# D5035-50.net
KiCad netlist of a schematic drawn in Altium Designer
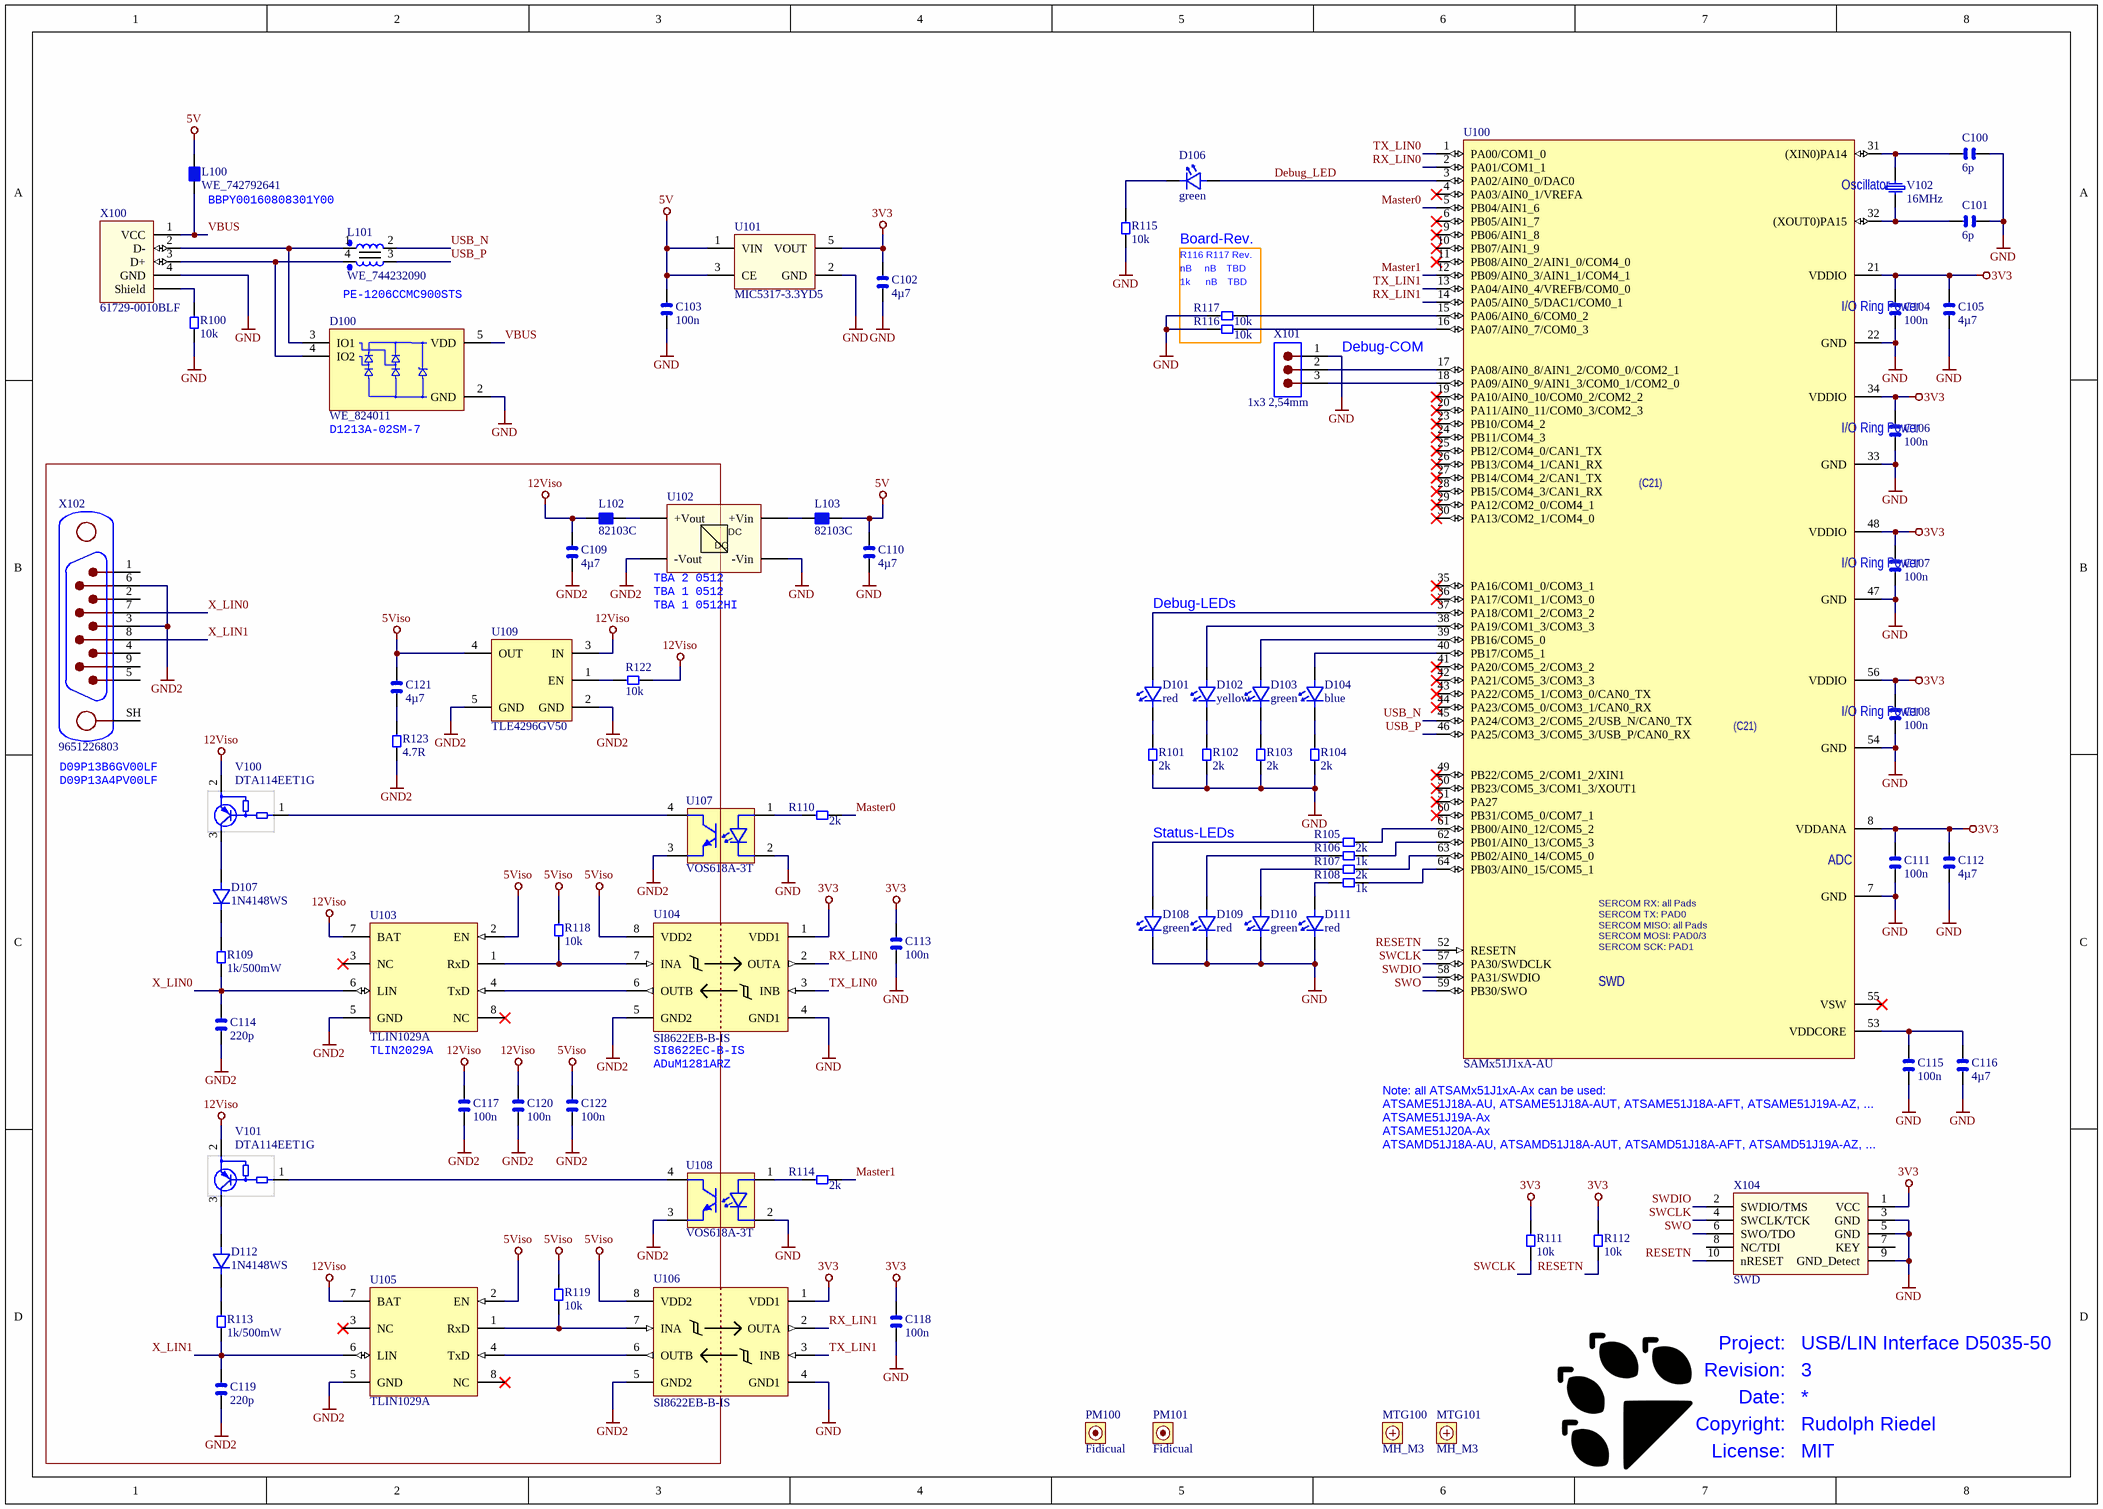
[diagram p0: D5035-50.SchDoc]

(export (version "E")
  (design (tool "Eeschema 10.0.6"))
  (components
    (comp (ref "C100")
      (value "6p")
      (footprint "CAPC1608X09L")
      (description "0603 Chip Capacitor")
      (fields (field (name "PART NUMBER") "CAPC_0603") (field (name "EDITOR") "rriedel"))
      (libsource (lib "HW-Labor_GF") (part "CAP_2_V2"))
    )
    (comp (ref "C101")
      (value "6p")
      (footprint "CAPC1608X09L")
      (description "0603 Chip Capacitor")
      (fields (field (name "PART NUMBER") "CAPC_0603") (field (name "EDITOR") "rriedel"))
      (libsource (lib "HW-Labor_GF") (part "CAP_2_V2"))
    )
    (comp (ref "C102")
      (value "4µ7")
      (footprint "CAPC2012X14L")
      (description "0805 Chip Capacitor")
      (fields (field (name "PART NUMBER") "CAPC_0805") (field (name "EDITOR") "rriedel"))
      (libsource (lib "HW-Labor_GF") (part "CAP_2_V2"))
    )
    (comp (ref "C103")
      (value "100n")
      (footprint "CAPC1608X09L")
      (description "0603 Chip Capacitor")
      (fields (field (name "PART NUMBER") "CAPC_0603") (field (name "EDITOR") "rriedel"))
      (libsource (lib "HW-Labor_GF") (part "CAP_2_V2"))
    )
    (comp (ref "C104")
      (value "100n")
      (footprint "CAPC1608X09L")
      (description "0603 Chip Capacitor")
      (fields (field (name "PART NUMBER") "CAPC_0603") (field (name "EDITOR") "rriedel"))
      (libsource (lib "HW-Labor_GF") (part "CAP_2_V2"))
    )
    (comp (ref "C105")
      (value "4µ7")
      (footprint "CAPC2012X14L")
      (description "0805 Chip Capacitor")
      (fields (field (name "PART NUMBER") "CAPC_0805") (field (name "EDITOR") "rriedel"))
      (libsource (lib "HW-Labor_GF") (part "CAP_2_V2"))
    )
    (comp (ref "C106")
      (value "100n")
      (footprint "CAPC1608X09L")
      (description "0603 Chip Capacitor")
      (fields (field (name "PART NUMBER") "CAPC_0603") (field (name "EDITOR") "rriedel"))
      (libsource (lib "HW-Labor_GF") (part "CAP_2_V2"))
    )
    (comp (ref "C107")
      (value "100n")
      (footprint "CAPC1608X09L")
      (description "0603 Chip Capacitor")
      (fields (field (name "PART NUMBER") "CAPC_0603") (field (name "EDITOR") "rriedel"))
      (libsource (lib "HW-Labor_GF") (part "CAP_2_V2"))
    )
    (comp (ref "C108")
      (value "100n")
      (footprint "CAPC1608X09L")
      (description "0603 Chip Capacitor")
      (fields (field (name "PART NUMBER") "CAPC_0603") (field (name "EDITOR") "rriedel"))
      (libsource (lib "HW-Labor_GF") (part "CAP_2_V2"))
    )
    (comp (ref "C109")
      (value "4µ7")
      (footprint "CAPC2012X14L")
      (description "0805 Chip Capacitor")
      (fields (field (name "PART NUMBER") "CAPC_0805") (field (name "EDITOR") "rriedel"))
      (libsource (lib "HW-Labor_GF") (part "CAP_2_V2"))
    )
    (comp (ref "C110")
      (value "4µ7")
      (footprint "CAPC2012X14L")
      (description "0805 Chip Capacitor")
      (fields (field (name "PART NUMBER") "CAPC_0805") (field (name "EDITOR") "rriedel"))
      (libsource (lib "HW-Labor_GF") (part "CAP_2_V2"))
    )
    (comp (ref "C111")
      (value "100n")
      (footprint "CAPC1608X09L")
      (description "0603 Chip Capacitor")
      (fields (field (name "PART NUMBER") "CAPC_0603") (field (name "EDITOR") "rriedel"))
      (libsource (lib "HW-Labor_GF") (part "CAP_2_V2"))
    )
    (comp (ref "C112")
      (value "4µ7")
      (footprint "CAPC2012X14L")
      (description "0805 Chip Capacitor")
      (fields (field (name "PART NUMBER") "CAPC_0805") (field (name "EDITOR") "rriedel"))
      (libsource (lib "HW-Labor_GF") (part "CAP_2_V2"))
    )
    (comp (ref "C113")
      (value "100n")
      (footprint "CAPC1608X09L")
      (description "0603 Chip Capacitor")
      (fields (field (name "PART NUMBER") "CAPC_0603") (field (name "EDITOR") "rriedel"))
      (libsource (lib "HW-Labor_GF") (part "CAP_2_V2"))
    )
    (comp (ref "C114")
      (value "220p")
      (footprint "CAPC2012X14L")
      (description "0805 Chip Capacitor")
      (fields (field (name "PART NUMBER") "CAPC_0805") (field (name "EDITOR") "rriedel"))
      (libsource (lib "HW-Labor_GF") (part "CAP_2_V2"))
    )
    (comp (ref "C115")
      (value "100n")
      (footprint "CAPC1608X09L")
      (description "0603 Chip Capacitor")
      (fields (field (name "PART NUMBER") "CAPC_0603") (field (name "EDITOR") "rriedel"))
      (libsource (lib "HW-Labor_GF") (part "CAP_2_V2"))
    )
    (comp (ref "C116")
      (value "4µ7")
      (footprint "CAPC2012X14L")
      (description "0805 Chip Capacitor")
      (fields (field (name "PART NUMBER") "CAPC_0805") (field (name "EDITOR") "rriedel"))
      (libsource (lib "HW-Labor_GF") (part "CAP_2_V2"))
    )
    (comp (ref "C117")
      (value "100n")
      (footprint "CAPC1608X09L")
      (description "0603 Chip Capacitor")
      (fields (field (name "PART NUMBER") "CAPC_0603") (field (name "EDITOR") "rriedel"))
      (libsource (lib "HW-Labor_GF") (part "CAP_2_V2"))
    )
    (comp (ref "C118")
      (value "100n")
      (footprint "CAPC1608X09L")
      (description "0603 Chip Capacitor")
      (fields (field (name "PART NUMBER") "CAPC_0603") (field (name "EDITOR") "rriedel"))
      (libsource (lib "HW-Labor_GF") (part "CAP_2_V2"))
    )
    (comp (ref "C119")
      (value "220p")
      (footprint "CAPC2012X14L")
      (description "0805 Chip Capacitor")
      (fields (field (name "PART NUMBER") "CAPC_0805") (field (name "EDITOR") "rriedel"))
      (libsource (lib "HW-Labor_GF") (part "CAP_2_V2"))
    )
    (comp (ref "C120")
      (value "100n")
      (footprint "CAPC1608X09L")
      (description "0603 Chip Capacitor")
      (fields (field (name "PART NUMBER") "CAPC_0603") (field (name "EDITOR") "rriedel"))
      (libsource (lib "HW-Labor_GF") (part "CAP_2_V2"))
    )
    (comp (ref "C121")
      (value "4µ7")
      (footprint "CAPC2012X14L")
      (description "0805 Chip Capacitor")
      (fields (field (name "PART NUMBER") "CAPC_0805") (field (name "EDITOR") "rriedel"))
      (libsource (lib "HW-Labor_GF") (part "CAP_2_V2"))
    )
    (comp (ref "C122")
      (value "100n")
      (footprint "CAPC1608X09L")
      (description "0603 Chip Capacitor")
      (fields (field (name "PART NUMBER") "CAPC_0603") (field (name "EDITOR") "rriedel"))
      (libsource (lib "HW-Labor_GF") (part "CAP_2_V2"))
    )
    (comp (ref "D100")
      (value "WE_824011")
      (footprint "SOT95P280X110-5N")
      (description "TVS Diode Array WE-TVS")
      (fields
        (field (name "MANUFACTURER") "Wuerth")
        (field (name "DISTRIBUTOR_1_PART_NUMBER") "732-4465-1-ND")
        (field (name "EDITOR") "rriedel")
      )
      (libsource (lib "HW-Labor_GF") (part "WE-824011"))
    )
    (comp (ref "D101")
      (value "red")
      (footprint "DIOC1608X06N_LED")
      (description "LED, 0603")
      (fields (field (name "PART NUMBER") "LED_0603") (field (name "EDITOR") "rriedel"))
      (libsource (lib "HW-Labor_GF") (part "LED_generic"))
    )
    (comp (ref "D102")
      (value "yellow")
      (footprint "DIOC1608X06N_LED")
      (description "LED, 0603")
      (fields (field (name "PART NUMBER") "LED_0603") (field (name "EDITOR") "rriedel"))
      (libsource (lib "HW-Labor_GF") (part "LED_generic"))
    )
    (comp (ref "D103")
      (value "green")
      (footprint "DIOC1608X06N_LED")
      (description "LED, 0603")
      (fields (field (name "PART NUMBER") "LED_0603") (field (name "EDITOR") "rriedel"))
      (libsource (lib "HW-Labor_GF") (part "LED_generic"))
    )
    (comp (ref "D104")
      (value "blue")
      (footprint "DIOC1608X06N_LED")
      (description "LED, 0603")
      (fields (field (name "PART NUMBER") "LED_0603") (field (name "EDITOR") "rriedel"))
      (libsource (lib "HW-Labor_GF") (part "LED_generic"))
    )
    (comp (ref "D106")
      (value "green")
      (footprint "DIOC1608X06N_LED")
      (description "LED, 0603")
      (fields (field (name "PART NUMBER") "LED_0603") (field (name "EDITOR") "rriedel"))
      (libsource (lib "HW-Labor_GF") (part "LED_generic"))
    )
    (comp (ref "D107")
      (value "1N4148WS")
      (footprint "SOD323")
      (description "Small Signal Diode IF 0.15A, VR 75V, SOD323F")
      (fields (field (name "DISTRIBUTOR_1_PART_NUMBER") "C2128") (field (name "EDITOR") "rriedel"))
      (libsource (lib "HW-Labor_GF") (part "Diode_A2_K1"))
    )
    (comp (ref "D108")
      (value "green")
      (footprint "DIOC1608X06N_LED")
      (description "LED, 0603")
      (fields (field (name "PART NUMBER") "LED_0603") (field (name "EDITOR") "rriedel"))
      (libsource (lib "HW-Labor_GF") (part "LED_generic"))
    )
    (comp (ref "D109")
      (value "red")
      (footprint "DIOC1608X06N_LED")
      (description "LED, 0603")
      (fields (field (name "PART NUMBER") "LED_0603") (field (name "EDITOR") "rriedel"))
      (libsource (lib "HW-Labor_GF") (part "LED_generic"))
    )
    (comp (ref "D110")
      (value "green")
      (footprint "DIOC1608X06N_LED")
      (description "LED, 0603")
      (fields (field (name "PART NUMBER") "LED_0603") (field (name "EDITOR") "rriedel"))
      (libsource (lib "HW-Labor_GF") (part "LED_generic"))
    )
    (comp (ref "D111")
      (value "red")
      (footprint "DIOC1608X06N_LED")
      (description "LED, 0603")
      (fields (field (name "PART NUMBER") "LED_0603") (field (name "EDITOR") "rriedel"))
      (libsource (lib "HW-Labor_GF") (part "LED_generic"))
    )
    (comp (ref "D112")
      (value "1N4148WS")
      (footprint "SOD323")
      (description "Small Signal Diode IF 0.15A, VR 75V, SOD323F")
      (fields (field (name "DISTRIBUTOR_1_PART_NUMBER") "C2128") (field (name "EDITOR") "rriedel"))
      (libsource (lib "HW-Labor_GF") (part "Diode_A2_K1"))
    )
    (comp (ref "L100")
      (value "WE_742792641")
      (footprint "INDC1608X06L")
      (description "SMT EMI suppression ferrite bead WE-CBF")
      (fields
        (field (name "MANUFACTURER") "Wuerth")
        (field (name "DISTRIBUTOR_1_PART_NUMBER") "732-1592-1-ND")
        (field (name "EDITOR") "rriedel")
      )
      (libsource (lib "HW-Labor_GF") (part "IND_2_V1"))
    )
    (comp (ref "L101")
      (value "WE_744232090")
      (footprint "WE_744232090")
      (description "SMD common mode noise suppressor WE-CNSW")
      (fields
        (field (name "MANUFACTURER") "Wuerth")
        (field (name "DISTRIBUTOR_1_PART_NUMBER") "732-1469-1-ND")
        (field (name "EDITOR") "rriedel")
      )
      (libsource (lib "HW-Labor_GF") (part "WE_744232090"))
    )
    (comp (ref "L102")
      (value "82103C")
      (footprint "Murata_8200C")
      (description "10µH, 0,5A, 400mR")
      (fields
        (field (name "MANUFACTURER") "Murata")
        (field (name "DISTRIBUTOR_1_PART_NUMBER") "811-2473-1-ND")
        (field (name "EDITOR") "rriedel")
      )
      (libsource (lib "HW-Labor_GF") (part "IND_2_V1"))
    )
    (comp (ref "L103")
      (value "82103C")
      (footprint "Murata_8200C")
      (description "10µH, 0,5A, 400mR")
      (fields
        (field (name "MANUFACTURER") "Murata")
        (field (name "DISTRIBUTOR_1_PART_NUMBER") "811-2473-1-ND")
        (field (name "EDITOR") "rriedel")
      )
      (libsource (lib "HW-Labor_GF") (part "IND_2_V1"))
    )
    (comp (ref "MTG100")
      (value "MH_M3")
      (footprint "HOLE_3_2MM")
      (description "Mounting-Hole for M3 screws")
      (fields (field (name "EDITOR") "rriedel"))
      (libsource (lib "HW-Labor_GF") (part "MTG_V1"))
    )
    (comp (ref "MTG101")
      (value "MH_M3")
      (footprint "HOLE_3_2MM")
      (description "Mounting-Hole for M3 screws")
      (fields (field (name "EDITOR") "rriedel"))
      (libsource (lib "HW-Labor_GF") (part "MTG_V1"))
    )
    (comp (ref "PM100")
      (value "Fidicual")
      (footprint "PM100")
      (fields (field (name "PART NUMBER") "PM100") (field (name "EDITOR") "rriedel"))
      (libsource (lib "HW-Labor_GF") (part "PM100"))
    )
    (comp (ref "PM101")
      (value "Fidicual")
      (footprint "PM100")
      (fields (field (name "PART NUMBER") "PM100") (field (name "EDITOR") "rriedel"))
      (libsource (lib "HW-Labor_GF") (part "PM100"))
    )
    (comp (ref "R100")
      (value "10k")
      (footprint "RESC1608X06L")
      (description "0603 Chip Resistor")
      (fields (field (name "PART NUMBER") "RESC_0603") (field (name "EDITOR") "rriedel"))
      (libsource (lib "HW-Labor_GF") (part "RES_2_V2"))
    )
    (comp (ref "R101")
      (value "2k")
      (footprint "RESC1608X06L")
      (description "0603 Chip Resistor")
      (fields (field (name "PART NUMBER") "RESC_0603") (field (name "EDITOR") "rriedel"))
      (libsource (lib "HW-Labor_GF") (part "RES_2_V2"))
    )
    (comp (ref "R102")
      (value "2k")
      (footprint "RESC1608X06L")
      (description "0603 Chip Resistor")
      (fields (field (name "PART NUMBER") "RESC_0603") (field (name "EDITOR") "rriedel"))
      (libsource (lib "HW-Labor_GF") (part "RES_2_V2"))
    )
    (comp (ref "R103")
      (value "2k")
      (footprint "RESC1608X06L")
      (description "0603 Chip Resistor")
      (fields (field (name "PART NUMBER") "RESC_0603") (field (name "EDITOR") "rriedel"))
      (libsource (lib "HW-Labor_GF") (part "RES_2_V2"))
    )
    (comp (ref "R104")
      (value "2k")
      (footprint "RESC1608X06L")
      (description "0603 Chip Resistor")
      (fields (field (name "PART NUMBER") "RESC_0603") (field (name "EDITOR") "rriedel"))
      (libsource (lib "HW-Labor_GF") (part "RES_2_V2"))
    )
    (comp (ref "R105")
      (value "2k")
      (footprint "RESC1608X06L")
      (description "0603 Chip Resistor")
      (fields (field (name "PART NUMBER") "RESC_0603") (field (name "EDITOR") "rriedel"))
      (libsource (lib "HW-Labor_GF") (part "RES_2_V2"))
    )
    (comp (ref "R106")
      (value "1k")
      (footprint "RESC1608X06L")
      (description "0603 Chip Resistor")
      (fields (field (name "PART NUMBER") "RESC_0603") (field (name "EDITOR") "rriedel"))
      (libsource (lib "HW-Labor_GF") (part "RES_2_V2"))
    )
    (comp (ref "R107")
      (value "2k")
      (footprint "RESC1608X06L")
      (description "0603 Chip Resistor")
      (fields (field (name "PART NUMBER") "RESC_0603") (field (name "EDITOR") "rriedel"))
      (libsource (lib "HW-Labor_GF") (part "RES_2_V2"))
    )
    (comp (ref "R108")
      (value "1k")
      (footprint "RESC1608X06L")
      (description "0603 Chip Resistor")
      (fields (field (name "PART NUMBER") "RESC_0603") (field (name "EDITOR") "rriedel"))
      (libsource (lib "HW-Labor_GF") (part "RES_2_V2"))
    )
    (comp (ref "R109")
      (value "1k/500mW")
      (footprint "RESC2012X06L")
      (description "0805 Chip Resistor")
      (fields (field (name "PART NUMBER") "RESC_0805") (field (name "EDITOR") "rriedel"))
      (libsource (lib "HW-Labor_GF") (part "RES_2_V2"))
    )
    (comp (ref "R110")
      (value "2k")
      (footprint "RESC1608X06L")
      (description "0603 Chip Resistor")
      (fields (field (name "PART NUMBER") "RESC_0603") (field (name "EDITOR") "rriedel"))
      (libsource (lib "HW-Labor_GF") (part "RES_2_V2"))
    )
    (comp (ref "R111")
      (value "10k")
      (footprint "RESC1608X06L")
      (description "0603 Chip Resistor")
      (fields (field (name "PART NUMBER") "RESC_0603") (field (name "EDITOR") "rriedel"))
      (libsource (lib "HW-Labor_GF") (part "RES_2_V2"))
    )
    (comp (ref "R112")
      (value "10k")
      (footprint "RESC1608X06L")
      (description "0603 Chip Resistor")
      (fields (field (name "PART NUMBER") "RESC_0603") (field (name "EDITOR") "rriedel"))
      (libsource (lib "HW-Labor_GF") (part "RES_2_V2"))
    )
    (comp (ref "R113")
      (value "1k/500mW")
      (footprint "RESC2012X06L")
      (description "0805 Chip Resistor")
      (fields (field (name "PART NUMBER") "RESC_0805") (field (name "EDITOR") "rriedel"))
      (libsource (lib "HW-Labor_GF") (part "RES_2_V2"))
    )
    (comp (ref "R114")
      (value "2k")
      (footprint "RESC1608X06L")
      (description "0603 Chip Resistor")
      (fields (field (name "PART NUMBER") "RESC_0603") (field (name "EDITOR") "rriedel"))
      (libsource (lib "HW-Labor_GF") (part "RES_2_V2"))
    )
    (comp (ref "R115")
      (value "10k")
      (footprint "RESC1608X06L")
      (description "0603 Chip Resistor")
      (fields (field (name "PART NUMBER") "RESC_0603") (field (name "EDITOR") "rriedel"))
      (libsource (lib "HW-Labor_GF") (part "RES_2_V2"))
    )
    (comp (ref "R116")
      (value "10k")
      (footprint "RESC1608X06L")
      (description "0603 Chip Resistor")
      (fields (field (name "PART NUMBER") "RESC_0603") (field (name "EDITOR") "rriedel"))
      (libsource (lib "HW-Labor_GF") (part "RES_2_V2"))
    )
    (comp (ref "R117")
      (value "10k")
      (footprint "RESC1608X06L")
      (description "0603 Chip Resistor")
      (fields (field (name "PART NUMBER") "RESC_0603") (field (name "EDITOR") "rriedel"))
      (libsource (lib "HW-Labor_GF") (part "RES_2_V2"))
    )
    (comp (ref "R118")
      (value "10k")
      (footprint "RESC1608X06L")
      (description "0603 Chip Resistor")
      (fields (field (name "PART NUMBER") "RESC_0603") (field (name "EDITOR") "rriedel"))
      (libsource (lib "HW-Labor_GF") (part "RES_2_V2"))
    )
    (comp (ref "R119")
      (value "10k")
      (footprint "RESC1608X06L")
      (description "0603 Chip Resistor")
      (fields (field (name "PART NUMBER") "RESC_0603") (field (name "EDITOR") "rriedel"))
      (libsource (lib "HW-Labor_GF") (part "RES_2_V2"))
    )
    (comp (ref "R122")
      (value "10k")
      (footprint "RESC1608X06L")
      (description "0603 Chip Resistor")
      (fields (field (name "PART NUMBER") "RESC_0603") (field (name "EDITOR") "rriedel"))
      (libsource (lib "HW-Labor_GF") (part "RES_2_V2"))
    )
    (comp (ref "R123")
      (value "4.7R")
      (footprint "RESC1608X06L")
      (description "0603 Chip Resistor")
      (fields (field (name "PART NUMBER") "RESC_0603") (field (name "EDITOR") "rriedel"))
      (libsource (lib "HW-Labor_GF") (part "RES_2_V2"))
    )
    (comp (ref "U100")
      (value "SAMx51J1xA-AU")
      (footprint "TSQFP50P1200X1200X120-64N")
      (description "32-bit Microcontroller, 120MHz Cortex M4-F, 512k FLASH,  2x CAN-FD, -40…85°C")
      (fields
        (field (name "PART NUMBER") "SAME51J19A-AU")
        (field (name "MANUFACTURER") "Microchip")
        (field (name "EDITOR") "rriedel")
      )
      (libsource (lib "HW-Labor_GF") (part "SAME5xJxxA-AUx"))
    )
    (comp (ref "U101")
      (value "MIC5317-3.3YD5")
      (footprint "SOT95P280X110-5N")
      (description "100 mA LDO,  Vout= 3,3V, -40°C..125°C")
      (fields (field (name "MANUFACTURER") "Microchip") (field (name "EDITOR") "rriedel"))
      (libsource (lib "HW-Labor_GF") (part "LDO_SOT23-5"))
    )
    (comp (ref "U102")
      (value "~")
      (footprint "TBA1/TBA2")
      (description "Isolated Single Output DC-DC Converters 5V/12V")
      (fields (field (name "PART NUMBER") "TBA 2-0512") (field (name "EDITOR") "rriedel"))
      (libsource (lib "HW-Labor_GF") (part "MER1SxxxxC"))
    )
    (comp (ref "U103")
      (value "TLIN1029A")
      (footprint "SOIC127P600X175-8N")
      (description "LIN transceiver")
      (fields
        (field (name "MANUFACTURER") "TI")
        (field (name "DISTRIBUTOR_1_PART_NUMBER") "595-TLIN1029ADRQ1")
        (field (name "EDITOR") "rriedel")
      )
      (libsource (lib "HW-Labor_GF") (part "TLIN1029A"))
    )
    (comp (ref "U104")
      (value "SI8622EB-B-IS")
      (footprint "SOIC127P600X175-8N")
      (description "Dual channel digital isolator, 150Mbit, 2,5kV")
      (fields
        (field (name "MANUFACTURER") "Silicon Labs")
        (field (name "DISTRIBUTOR_1_PART_NUMBER") "336-5209-1-ND")
        (field (name "EDITOR") "rriedel")
      )
      (libsource (lib "HW-Labor_GF") (part "SI8622"))
    )
    (comp (ref "U105")
      (value "TLIN1029A")
      (footprint "SOIC127P600X175-8N")
      (description "LIN transceiver")
      (fields
        (field (name "MANUFACTURER") "TI")
        (field (name "DISTRIBUTOR_1_PART_NUMBER") "595-TLIN1029ADRQ1")
        (field (name "EDITOR") "rriedel")
      )
      (libsource (lib "HW-Labor_GF") (part "TLIN1029A"))
    )
    (comp (ref "U106")
      (value "SI8622EB-B-IS")
      (footprint "SOIC127P600X175-8N")
      (description "Dual channel digital isolator, 150Mbit, 2,5kV")
      (fields
        (field (name "MANUFACTURER") "Silicon Labs")
        (field (name "DISTRIBUTOR_1_PART_NUMBER") "336-5209-1-ND")
        (field (name "EDITOR") "rriedel")
      )
      (libsource (lib "HW-Labor_GF") (part "SI8622"))
    )
    (comp (ref "U107")
      (value "VOS618A-3T")
      (footprint "SSOP-4")
      (description "Optocoupler, Phototransistor Output, Low Input Current, SSOP-4")
      (fields
        (field (name "MANUFACTURER") "Vishay")
        (field (name "DISTRIBUTOR_1_PART_NUMBER") "VOS618A-3TCT-ND‎")
        (field (name "EDITOR") "rriedel")
      )
      (libsource (lib "HW-Labor_GF") (part "VOS618A"))
    )
    (comp (ref "U108")
      (value "VOS618A-3T")
      (footprint "SSOP-4")
      (description "Optocoupler, Phototransistor Output, Low Input Current, SSOP-4")
      (fields
        (field (name "MANUFACTURER") "Vishay")
        (field (name "DISTRIBUTOR_1_PART_NUMBER") "VOS618A-3TCT-ND‎")
        (field (name "EDITOR") "rriedel")
      )
      (libsource (lib "HW-Labor_GF") (part "VOS618A"))
    )
    (comp (ref "U109")
      (value "TLE4296GV50")
      (footprint "INF-PG-SCT595V")
      (description "30 mA LDO, Vout = 5,0V, 4%")
      (fields (field (name "MANUFACTURER") "Infineon") (field (name "EDITOR") "rriedel"))
      (libsource (lib "HW-Labor_GF") (part "TLE4295GVxx"))
    )
    (comp (ref "V100")
      (value "DTA114EET1G")
      (footprint "SOT50P162X60-3N")
      (description "PNP Transistor with Resistors (10kΩ, 10kΩ)  VCE= 50V, IC=100mA, SOT23, AEC Q101")
      (fields (field (name "EDITOR") "rriedel"))
      (libsource (lib "HW-Labor_GF") (part "PNP_Digital"))
    )
    (comp (ref "V101")
      (value "DTA114EET1G")
      (footprint "SOT50P162X60-3N")
      (description "PNP Transistor with Resistors (10kΩ, 10kΩ)  VCE= 50V, IC=100mA, SOT23, AEC Q101")
      (fields (field (name "EDITOR") "rriedel"))
      (libsource (lib "HW-Labor_GF") (part "PNP_Digital"))
    )
    (comp (ref "V102")
      (value "16MHz")
      (footprint "NX3225Gx")
      (description "16.000MHz Crystal SMD, 3.2x2.5mm, 8pF, 50ppm,  -40..+150°C")
      (fields
        (field (name "PART NUMBER") "NX3225GB-16.000000MHZ")
        (field (name "MANUFACTURER") "NDK")
        (field (name "EDITOR") "rriedel")
      )
      (libsource (lib "HW-Labor_GF") (part "XTAL_2_V1"))
    )
    (comp (ref "X100")
      (value "61729-0010BLF")
      (footprint "61729-xxxxxLF")
      (description "USB-B socket, THT")
      (fields
        (field (name "MANUFACTURER") "Amphenol")
        (field (name "DISTRIBUTOR_1_PART_NUMBER") "609-1039-ND")
        (field (name "EDITOR") "rriedel")
      )
      (libsource (lib "HW-Labor_GF") (part "USB"))
    )
    (comp (ref "X101")
      (value "1x3 2,54mm")
      (footprint "PINH_1x03_2_54mm")
      (description "Pin-Header 2,54 mm 3pins")
      (fields (field (name "PART NUMBER") "PINH_1x3_2_54") (field (name "EDITOR") "rriedel"))
      (libsource (lib "HW-Labor_GF") (part "CONM_1x3_V2"))
    )
    (comp (ref "X102")
      (value "9651226803")
      (footprint "09651226803")
      (description "D-Sub, 9 pin, male, right angle")
      (fields
        (field (name "MANUFACTURER") "Harting")
        (field (name "DISTRIBUTOR_1_PART_NUMBER") "2752007")
        (field (name "EDITOR") "rriedel")
      )
      (libsource (lib "HW-Labor_GF") (part "D_Sub_9_Male"))
    )
    (comp (ref "X104")
      (value "SWD")
      (footprint "FTSH-105-01-L-DV-K")
      (description "ARM Debug-Header 2x5 1,27 mm")
      (fields (field (name "EDITOR") "rriedel"))
      (libsource (lib "HW-Labor_GF") (part "SWD"))
    )
  )
  (nets
    (net (code "1") (name "/Debug_LED") (class "Default")
      (node (ref "D106") (pin "2") (pinfunction "2_2") (pintype "passive"))
      (node (ref "U100") (pin "3") (pinfunction "PA02/AIN0_0/DAC0_3") (pintype "bidirectional"))
    )
    (net (code "2") (name "/Master0") (class "Default")
      (node (ref "R110") (pin "1") (pinfunction "1_1") (pintype "passive"))
      (node (ref "U100") (pin "5") (pinfunction "PB04/AIN1_6_5") (pintype "bidirectional"))
    )
    (net (code "3") (name "/Master1") (class "Default")
      (node (ref "R114") (pin "1") (pinfunction "1_1") (pintype "passive"))
      (node (ref "U100") (pin "12") (pinfunction "PB09/AIN0_3/AIN1_1/COM4_1_12") (pintype "bidirectional"))
    )
    (net (code "4") (name "/RESETN") (class "Default")
      (node (ref "R112") (pin "2") (pinfunction "2_2") (pintype "passive"))
      (node (ref "U100") (pin "52") (pinfunction "RESETN_52") (pintype "input"))
      (node (ref "X104") (pin "10") (pinfunction "nRESET_10") (pintype "passive"))
    )
    (net (code "5") (name "/RX_LIN0") (class "Default")
      (node (ref "U100") (pin "2") (pinfunction "PA01/COM1_1_2") (pintype "bidirectional"))
      (node (ref "U104") (pin "2") (pinfunction "OUTA_2") (pintype "output"))
    )
    (net (code "6") (name "/RX_LIN1") (class "Default")
      (node (ref "U100") (pin "14") (pinfunction "PA05/AIN0_5/DAC1/COM0_1_14") (pintype "bidirectional"))
      (node (ref "U106") (pin "2") (pinfunction "OUTA_2") (pintype "output"))
    )
    (net (code "7") (name "/SWCLK") (class "Default")
      (node (ref "R111") (pin "2") (pinfunction "2_2") (pintype "passive"))
      (node (ref "U100") (pin "57") (pinfunction "PA30/SWDCLK_57") (pintype "bidirectional"))
      (node (ref "X104") (pin "4") (pinfunction "SWCLK/TCK_4") (pintype "passive"))
    )
    (net (code "8") (name "/SWDIO") (class "Default")
      (node (ref "U100") (pin "58") (pinfunction "PA31/SWDIO_58") (pintype "bidirectional"))
      (node (ref "X104") (pin "2") (pinfunction "SWDIO/TMS_2") (pintype "passive"))
    )
    (net (code "9") (name "/SWO") (class "Default")
      (node (ref "U100") (pin "59") (pinfunction "PB30/SWO_59") (pintype "bidirectional"))
      (node (ref "X104") (pin "6") (pinfunction "SWO/TDO_6") (pintype "passive"))
    )
    (net (code "10") (name "/TX_LIN0") (class "Default")
      (node (ref "U100") (pin "1") (pinfunction "PA00/COM1_0_1") (pintype "bidirectional"))
      (node (ref "U104") (pin "3") (pinfunction "INB_3") (pintype "input"))
    )
    (net (code "11") (name "/TX_LIN1") (class "Default")
      (node (ref "U100") (pin "13") (pinfunction "PA04/AIN0_4/VREFB/COM0_0_13") (pintype "bidirectional"))
      (node (ref "U106") (pin "3") (pinfunction "INB_3") (pintype "input"))
    )
    (net (code "12") (name "/USB_N") (class "Default")
      (node (ref "L101") (pin "2") (pinfunction "2_2") (pintype "passive"))
      (node (ref "U100") (pin "45") (pinfunction "PA24/COM3_2/COM5_2/USB_N/CAN0_TX_45") (pintype "bidirectional"))
    )
    (net (code "13") (name "/USB_P") (class "Default")
      (node (ref "L101") (pin "3") (pinfunction "3_3") (pintype "passive"))
      (node (ref "U100") (pin "46") (pinfunction "PA25/COM3_3/COM5_3/USB_P/CAN0_RX_46") (pintype "bidirectional"))
    )
    (net (code "14") (name "/VBUS") (class "Default")
      (node (ref "D100") (pin "5") (pinfunction "VDD_5") (pintype "passive"))
      (node (ref "L100") (pin "1") (pinfunction "1_1") (pintype "passive"))
      (node (ref "X100") (pin "1") (pinfunction "VCC_1") (pintype "power_in"))
    )
    (net (code "15") (name "/X_LIN0") (class "Default")
      (node (ref "C114") (pin "2") (pinfunction "2_2") (pintype "passive"))
      (node (ref "R109") (pin "1") (pinfunction "1_1") (pintype "passive"))
      (node (ref "U103") (pin "6") (pinfunction "LIN_6") (pintype "bidirectional"))
      (node (ref "X102") (pin "7") (pinfunction "7_7") (pintype "passive"))
    )
    (net (code "16") (name "/X_LIN1") (class "Default")
      (node (ref "C119") (pin "2") (pinfunction "2_2") (pintype "passive"))
      (node (ref "R113") (pin "1") (pinfunction "1_1") (pintype "passive"))
      (node (ref "U105") (pin "6") (pinfunction "LIN_6") (pintype "bidirectional"))
      (node (ref "X102") (pin "8") (pinfunction "8_8") (pintype "passive"))
    )
    (net (code "17") (name "3V3") (class "Default")
      (node (ref "C102") (pin "2") (pinfunction "2_2") (pintype "passive"))
      (node (ref "C104") (pin "2") (pinfunction "2_2") (pintype "passive"))
      (node (ref "C105") (pin "2") (pinfunction "2_2") (pintype "passive"))
      (node (ref "C106") (pin "2") (pinfunction "2_2") (pintype "passive"))
      (node (ref "C107") (pin "2") (pinfunction "2_2") (pintype "passive"))
      (node (ref "C108") (pin "2") (pinfunction "2_2") (pintype "passive"))
      (node (ref "C111") (pin "2") (pinfunction "2_2") (pintype "passive"))
      (node (ref "C112") (pin "2") (pinfunction "2_2") (pintype "passive"))
      (node (ref "C113") (pin "2") (pinfunction "2_2") (pintype "passive"))
      (node (ref "C118") (pin "2") (pinfunction "2_2") (pintype "passive"))
      (node (ref "R111") (pin "1") (pinfunction "1_1") (pintype "passive"))
      (node (ref "R112") (pin "1") (pinfunction "1_1") (pintype "passive"))
      (node (ref "U100") (pin "21") (pinfunction "VDDIO_21") (pintype "power_in"))
      (node (ref "U100") (pin "34") (pinfunction "VDDIO_34") (pintype "power_in"))
      (node (ref "U100") (pin "48") (pinfunction "VDDIO_48") (pintype "power_in"))
      (node (ref "U100") (pin "56") (pinfunction "VDDIO_56") (pintype "power_in"))
      (node (ref "U100") (pin "8") (pinfunction "VDDANA_8") (pintype "power_in"))
      (node (ref "U101") (pin "5") (pinfunction "VOUT_5") (pintype "passive"))
      (node (ref "U104") (pin "1") (pinfunction "VDD1_1") (pintype "power_in"))
      (node (ref "U106") (pin "1") (pinfunction "VDD1_1") (pintype "power_in"))
      (node (ref "X104") (pin "1") (pinfunction "VCC_1") (pintype "power_in"))
    )
    (net (code "18") (name "5V") (class "Default")
      (node (ref "C103") (pin "2") (pinfunction "2_2") (pintype "passive"))
      (node (ref "C110") (pin "2") (pinfunction "2_2") (pintype "passive"))
      (node (ref "L100") (pin "2") (pinfunction "2_2") (pintype "passive"))
      (node (ref "L103") (pin "1") (pinfunction "1_1") (pintype "passive"))
      (node (ref "U101") (pin "1") (pinfunction "VIN_1") (pintype "passive"))
      (node (ref "U101") (pin "3") (pinfunction "CE_3") (pintype "passive"))
    )
    (net (code "19") (name "5Viso") (class "Default")
      (node (ref "C121") (pin "2") (pinfunction "2_2") (pintype "passive"))
      (node (ref "C122") (pin "2") (pinfunction "2_2") (pintype "passive"))
      (node (ref "R118") (pin "1") (pinfunction "1_1") (pintype "passive"))
      (node (ref "R119") (pin "1") (pinfunction "1_1") (pintype "passive"))
      (node (ref "U103") (pin "2") (pinfunction "EN_2") (pintype "input"))
      (node (ref "U104") (pin "8") (pinfunction "VDD2_8") (pintype "power_in"))
      (node (ref "U105") (pin "2") (pinfunction "EN_2") (pintype "input"))
      (node (ref "U106") (pin "8") (pinfunction "VDD2_8") (pintype "power_in"))
      (node (ref "U109") (pin "4") (pinfunction "OUT_4") (pintype "passive"))
    )
    (net (code "20") (name "12Viso") (class "Default")
      (node (ref "C109") (pin "2") (pinfunction "2_2") (pintype "passive"))
      (node (ref "C117") (pin "2") (pinfunction "2_2") (pintype "passive"))
      (node (ref "C120") (pin "2") (pinfunction "2_2") (pintype "passive"))
      (node (ref "L102") (pin "2") (pinfunction "2_2") (pintype "passive"))
      (node (ref "R122") (pin "2") (pinfunction "2_2") (pintype "passive"))
      (node (ref "U103") (pin "7") (pinfunction "BAT_7") (pintype "power_in"))
      (node (ref "U105") (pin "7") (pinfunction "BAT_7") (pintype "power_in"))
      (node (ref "U109") (pin "3") (pinfunction "IN_3") (pintype "passive"))
      (node (ref "V100") (pin "2") (pinfunction "2_2") (pintype "passive"))
      (node (ref "V101") (pin "2") (pinfunction "2_2") (pintype "passive"))
    )
    (net (code "21") (name "GND") (class "Default")
      (node (ref "C100") (pin "2") (pinfunction "2_2") (pintype "passive"))
      (node (ref "C101") (pin "1") (pinfunction "1_1") (pintype "passive"))
      (node (ref "C102") (pin "1") (pinfunction "1_1") (pintype "passive"))
      (node (ref "C103") (pin "1") (pinfunction "1_1") (pintype "passive"))
      (node (ref "C104") (pin "1") (pinfunction "1_1") (pintype "passive"))
      (node (ref "C105") (pin "1") (pinfunction "1_1") (pintype "passive"))
      (node (ref "C106") (pin "1") (pinfunction "1_1") (pintype "passive"))
      (node (ref "C107") (pin "1") (pinfunction "1_1") (pintype "passive"))
      (node (ref "C108") (pin "1") (pinfunction "1_1") (pintype "passive"))
      (node (ref "C110") (pin "1") (pinfunction "1_1") (pintype "passive"))
      (node (ref "C111") (pin "1") (pinfunction "1_1") (pintype "passive"))
      (node (ref "C112") (pin "1") (pinfunction "1_1") (pintype "passive"))
      (node (ref "C113") (pin "1") (pinfunction "1_1") (pintype "passive"))
      (node (ref "C115") (pin "1") (pinfunction "1_1") (pintype "passive"))
      (node (ref "C116") (pin "1") (pinfunction "1_1") (pintype "passive"))
      (node (ref "C118") (pin "1") (pinfunction "1_1") (pintype "passive"))
      (node (ref "D100") (pin "2") (pinfunction "GND_2") (pintype "passive"))
      (node (ref "D108") (pin "1") (pinfunction "1_1") (pintype "passive"))
      (node (ref "D109") (pin "1") (pinfunction "1_1") (pintype "passive"))
      (node (ref "D110") (pin "1") (pinfunction "1_1") (pintype "passive"))
      (node (ref "D111") (pin "1") (pinfunction "1_1") (pintype "passive"))
      (node (ref "R100") (pin "1") (pinfunction "1_1") (pintype "passive"))
      (node (ref "R101") (pin "1") (pinfunction "1_1") (pintype "passive"))
      (node (ref "R102") (pin "1") (pinfunction "1_1") (pintype "passive"))
      (node (ref "R103") (pin "1") (pinfunction "1_1") (pintype "passive"))
      (node (ref "R104") (pin "1") (pinfunction "1_1") (pintype "passive"))
      (node (ref "R115") (pin "1") (pinfunction "1_1") (pintype "passive"))
      (node (ref "R116") (pin "2") (pinfunction "2_2") (pintype "passive"))
      (node (ref "R117") (pin "2") (pinfunction "2_2") (pintype "passive"))
      (node (ref "U100") (pin "22") (pinfunction "GND_22") (pintype "power_in"))
      (node (ref "U100") (pin "33") (pinfunction "GND_33") (pintype "power_in"))
      (node (ref "U100") (pin "47") (pinfunction "GND_47") (pintype "power_in"))
      (node (ref "U100") (pin "54") (pinfunction "GND_54") (pintype "power_in"))
      (node (ref "U100") (pin "7") (pinfunction "GND_7") (pintype "power_in"))
      (node (ref "U101") (pin "2") (pinfunction "GND_2") (pintype "passive"))
      (node (ref "U102") (pin "2") (pinfunction "-Vin_2") (pintype "power_in"))
      (node (ref "U104") (pin "4") (pinfunction "GND1_4") (pintype "power_in"))
      (node (ref "U106") (pin "4") (pinfunction "GND1_4") (pintype "power_in"))
      (node (ref "U107") (pin "2") (pinfunction "C_2") (pintype "passive"))
      (node (ref "U108") (pin "2") (pinfunction "C_2") (pintype "passive"))
      (node (ref "X100") (pin "4") (pinfunction "GND_4") (pintype "power_in"))
      (node (ref "X101") (pin "1") (pinfunction "1_1") (pintype "passive"))
      (node (ref "X104") (pin "3") (pinfunction "GND_3") (pintype "power_in"))
      (node (ref "X104") (pin "5") (pinfunction "GND_5") (pintype "power_in"))
      (node (ref "X104") (pin "9") (pinfunction "GND_Detect_9") (pintype "power_in"))
    )
    (net (code "22") (name "GND2") (class "Default")
      (node (ref "C109") (pin "1") (pinfunction "1_1") (pintype "passive"))
      (node (ref "C114") (pin "1") (pinfunction "1_1") (pintype "passive"))
      (node (ref "C117") (pin "1") (pinfunction "1_1") (pintype "passive"))
      (node (ref "C119") (pin "1") (pinfunction "1_1") (pintype "passive"))
      (node (ref "C120") (pin "1") (pinfunction "1_1") (pintype "passive"))
      (node (ref "C122") (pin "1") (pinfunction "1_1") (pintype "passive"))
      (node (ref "R123") (pin "2") (pinfunction "2_2") (pintype "passive"))
      (node (ref "U102") (pin "4") (pinfunction "-Vout_4") (pintype "power_in"))
      (node (ref "U103") (pin "5") (pinfunction "GND_5") (pintype "power_in"))
      (node (ref "U104") (pin "5") (pinfunction "GND2_5") (pintype "power_in"))
      (node (ref "U105") (pin "5") (pinfunction "GND_5") (pintype "power_in"))
      (node (ref "U106") (pin "5") (pinfunction "GND2_5") (pintype "power_in"))
      (node (ref "U107") (pin "3") (pinfunction "E_3") (pintype "passive"))
      (node (ref "U108") (pin "3") (pinfunction "E_3") (pintype "passive"))
      (node (ref "U109") (pin "2") (pinfunction "GND_2") (pintype "passive"))
      (node (ref "U109") (pin "5") (pinfunction "GND_5") (pintype "passive"))
      (node (ref "X102") (pin "3") (pinfunction "3_3") (pintype "passive"))
      (node (ref "X102") (pin "6") (pinfunction "6_6") (pintype "passive"))
    )
    (net (code "23") (name "Net-(C121-Pad1)") (class "Default")
      (node (ref "C121") (pin "1") (pinfunction "1_1") (pintype "passive"))
      (node (ref "R123") (pin "1") (pinfunction "1_1") (pintype "passive"))
    )
    (net (code "24") (name "Net-(D100-IO1)") (class "Default")
      (node (ref "D100") (pin "3") (pinfunction "IO1_3") (pintype "passive"))
      (node (ref "L101") (pin "1") (pinfunction "1_1") (pintype "passive"))
      (node (ref "X100") (pin "2") (pinfunction "D-_2") (pintype "bidirectional"))
    )
    (net (code "25") (name "Net-(D100-IO2)") (class "Default")
      (node (ref "D100") (pin "4") (pinfunction "IO2_4") (pintype "passive"))
      (node (ref "L101") (pin "4") (pinfunction "4_4") (pintype "passive"))
      (node (ref "X100") (pin "3") (pinfunction "D+_3") (pintype "bidirectional"))
    )
    (net (code "26") (name "Net-(D101-Pad1)") (class "Default")
      (node (ref "D101") (pin "1") (pinfunction "1_1") (pintype "passive"))
      (node (ref "R101") (pin "2") (pinfunction "2_2") (pintype "passive"))
    )
    (net (code "27") (name "Net-(D102-Pad1)") (class "Default")
      (node (ref "D102") (pin "1") (pinfunction "1_1") (pintype "passive"))
      (node (ref "R102") (pin "2") (pinfunction "2_2") (pintype "passive"))
    )
    (net (code "28") (name "Net-(D103-Pad1)") (class "Default")
      (node (ref "D103") (pin "1") (pinfunction "1_1") (pintype "passive"))
      (node (ref "R103") (pin "2") (pinfunction "2_2") (pintype "passive"))
    )
    (net (code "29") (name "Net-(D104-Pad1)") (class "Default")
      (node (ref "D104") (pin "1") (pinfunction "1_1") (pintype "passive"))
      (node (ref "R104") (pin "2") (pinfunction "2_2") (pintype "passive"))
    )
    (net (code "30") (name "Net-(D106-Pad1)") (class "Default")
      (node (ref "D106") (pin "1") (pinfunction "1_1") (pintype "passive"))
      (node (ref "R115") (pin "2") (pinfunction "2_2") (pintype "passive"))
    )
    (net (code "31") (name "Net-(D107-Pad1)") (class "Default")
      (node (ref "D107") (pin "1") (pinfunction "1_1") (pintype "passive"))
      (node (ref "R109") (pin "2") (pinfunction "2_2") (pintype "passive"))
    )
    (net (code "32") (name "Net-(D107-Pad2)") (class "Default")
      (node (ref "D107") (pin "2") (pinfunction "2_2") (pintype "passive"))
      (node (ref "V100") (pin "3") (pinfunction "3_3") (pintype "passive"))
    )
    (net (code "33") (name "Net-(D108-Pad2)") (class "Default")
      (node (ref "D108") (pin "2") (pinfunction "2_2") (pintype "passive"))
      (node (ref "R105") (pin "1") (pinfunction "1_1") (pintype "passive"))
    )
    (net (code "34") (name "Net-(D109-Pad2)") (class "Default")
      (node (ref "D109") (pin "2") (pinfunction "2_2") (pintype "passive"))
      (node (ref "R106") (pin "1") (pinfunction "1_1") (pintype "passive"))
    )
    (net (code "35") (name "Net-(D110-Pad2)") (class "Default")
      (node (ref "D110") (pin "2") (pinfunction "2_2") (pintype "passive"))
      (node (ref "R107") (pin "1") (pinfunction "1_1") (pintype "passive"))
    )
    (net (code "36") (name "Net-(D111-Pad2)") (class "Default")
      (node (ref "D111") (pin "2") (pinfunction "2_2") (pintype "passive"))
      (node (ref "R108") (pin "1") (pinfunction "1_1") (pintype "passive"))
    )
    (net (code "37") (name "Net-(D112-Pad1)") (class "Default")
      (node (ref "D112") (pin "1") (pinfunction "1_1") (pintype "passive"))
      (node (ref "R113") (pin "2") (pinfunction "2_2") (pintype "passive"))
    )
    (net (code "38") (name "Net-(D112-Pad2)") (class "Default")
      (node (ref "D112") (pin "2") (pinfunction "2_2") (pintype "passive"))
      (node (ref "V101") (pin "3") (pinfunction "3_3") (pintype "passive"))
    )
    (net (code "39") (name "Net-(U100-(XIN0)PA14)") (class "Default")
      (node (ref "C100") (pin "1") (pinfunction "1_1") (pintype "passive"))
      (node (ref "U100") (pin "31") (pinfunction "(XIN0)PA14_31") (pintype "bidirectional"))
      (node (ref "V102") (pin "2") (pinfunction "2_2") (pintype "passive"))
    )
    (net (code "40") (name "Net-(U100-(XOUT0)PA15)") (class "Default")
      (node (ref "C101") (pin "2") (pinfunction "2_2") (pintype "passive"))
      (node (ref "U100") (pin "32") (pinfunction "(XOUT0)PA15_32") (pintype "bidirectional"))
      (node (ref "V102") (pin "1") (pinfunction "1_1") (pintype "passive"))
    )
    (net (code "41") (name "Net-(U100-PA06{slash}AIN0_6{slash}COM0_2)") (class "Default")
      (node (ref "R117") (pin "1") (pinfunction "1_1") (pintype "passive"))
      (node (ref "U100") (pin "15") (pinfunction "PA06/AIN0_6/COM0_2_15") (pintype "bidirectional"))
    )
    (net (code "42") (name "Net-(U100-PA07{slash}AIN0_7{slash}COM0_3)") (class "Default")
      (node (ref "R116") (pin "1") (pinfunction "1_1") (pintype "passive"))
      (node (ref "U100") (pin "16") (pinfunction "PA07/AIN0_7/COM0_3_16") (pintype "bidirectional"))
    )
    (net (code "43") (name "Net-(U100-PA08{slash}AIN0_8{slash}AIN1_2{slash}COM0_0{slash}COM2_1)") (class "Default")
      (node (ref "U100") (pin "17") (pinfunction "PA08/AIN0_8/AIN1_2/COM0_0/COM2_1_17") (pintype "bidirectional"))
      (node (ref "X101") (pin "2") (pinfunction "2_2") (pintype "passive"))
    )
    (net (code "44") (name "Net-(U100-PA09{slash}AIN0_9{slash}AIN1_3{slash}COM0_1{slash}COM2_0)") (class "Default")
      (node (ref "U100") (pin "18") (pinfunction "PA09/AIN0_9/AIN1_3/COM0_1/COM2_0_18") (pintype "bidirectional"))
      (node (ref "X101") (pin "3") (pinfunction "3_3") (pintype "passive"))
    )
    (net (code "45") (name "Net-(U100-PA18{slash}COM1_2{slash}COM3_2)") (class "Default")
      (node (ref "D101") (pin "2") (pinfunction "2_2") (pintype "passive"))
      (node (ref "U100") (pin "37") (pinfunction "PA18/COM1_2/COM3_2_37") (pintype "bidirectional"))
    )
    (net (code "46") (name "Net-(U100-PA19{slash}COM1_3{slash}COM3_3)") (class "Default")
      (node (ref "D102") (pin "2") (pinfunction "2_2") (pintype "passive"))
      (node (ref "U100") (pin "38") (pinfunction "PA19/COM1_3/COM3_3_38") (pintype "bidirectional"))
    )
    (net (code "47") (name "Net-(U100-PB00{slash}AIN0_12{slash}COM5_2)") (class "Default")
      (node (ref "R105") (pin "2") (pinfunction "2_2") (pintype "passive"))
      (node (ref "U100") (pin "61") (pinfunction "PB00/AIN0_12/COM5_2_61") (pintype "bidirectional"))
    )
    (net (code "48") (name "Net-(U100-PB01{slash}AIN0_13{slash}COM5_3)") (class "Default")
      (node (ref "R106") (pin "2") (pinfunction "2_2") (pintype "passive"))
      (node (ref "U100") (pin "62") (pinfunction "PB01/AIN0_13/COM5_3_62") (pintype "bidirectional"))
    )
    (net (code "49") (name "Net-(U100-PB02{slash}AIN0_14{slash}COM5_0)") (class "Default")
      (node (ref "R107") (pin "2") (pinfunction "2_2") (pintype "passive"))
      (node (ref "U100") (pin "63") (pinfunction "PB02/AIN0_14/COM5_0_63") (pintype "bidirectional"))
    )
    (net (code "50") (name "Net-(U100-PB03{slash}AIN0_15{slash}COM5_1)") (class "Default")
      (node (ref "R108") (pin "2") (pinfunction "2_2") (pintype "passive"))
      (node (ref "U100") (pin "64") (pinfunction "PB03/AIN0_15/COM5_1_64") (pintype "bidirectional"))
    )
    (net (code "51") (name "Net-(U100-PB16{slash}COM5_0)") (class "Default")
      (node (ref "D103") (pin "2") (pinfunction "2_2") (pintype "passive"))
      (node (ref "U100") (pin "39") (pinfunction "PB16/COM5_0_39") (pintype "bidirectional"))
    )
    (net (code "52") (name "Net-(U100-PB17{slash}COM5_1)") (class "Default")
      (node (ref "D104") (pin "2") (pinfunction "2_2") (pintype "passive"))
      (node (ref "U100") (pin "40") (pinfunction "PB17/COM5_1_40") (pintype "bidirectional"))
    )
    (net (code "53") (name "Net-(U100-VDDCORE)") (class "Default")
      (node (ref "C115") (pin "2") (pinfunction "2_2") (pintype "passive"))
      (node (ref "C116") (pin "2") (pinfunction "2_2") (pintype "passive"))
      (node (ref "U100") (pin "53") (pinfunction "VDDCORE_53") (pintype "passive"))
    )
    (net (code "54") (name "Net-(U102-+Vin)") (class "Default")
      (node (ref "L103") (pin "2") (pinfunction "2_2") (pintype "passive"))
      (node (ref "U102") (pin "1") (pinfunction "+Vin_1") (pintype "power_in"))
    )
    (net (code "55") (name "Net-(U102-+Vout)") (class "Default")
      (node (ref "L102") (pin "1") (pinfunction "1_1") (pintype "passive"))
      (node (ref "U102") (pin "6") (pinfunction "+Vout_6") (pintype "power_in"))
    )
    (net (code "56") (name "Net-(U103-RxD)") (class "Default")
      (node (ref "R118") (pin "2") (pinfunction "2_2") (pintype "passive"))
      (node (ref "U103") (pin "1") (pinfunction "RxD_1") (pintype "open_collector"))
      (node (ref "U104") (pin "7") (pinfunction "INA_7") (pintype "input"))
    )
    (net (code "57") (name "Net-(U103-TxD)") (class "Default")
      (node (ref "U103") (pin "4") (pinfunction "TxD_4") (pintype "input"))
      (node (ref "U104") (pin "6") (pinfunction "OUTB_6") (pintype "output"))
    )
    (net (code "58") (name "Net-(U105-RxD)") (class "Default")
      (node (ref "R119") (pin "2") (pinfunction "2_2") (pintype "passive"))
      (node (ref "U105") (pin "1") (pinfunction "RxD_1") (pintype "open_collector"))
      (node (ref "U106") (pin "7") (pinfunction "INA_7") (pintype "input"))
    )
    (net (code "59") (name "Net-(U105-TxD)") (class "Default")
      (node (ref "U105") (pin "4") (pinfunction "TxD_4") (pintype "input"))
      (node (ref "U106") (pin "6") (pinfunction "OUTB_6") (pintype "output"))
    )
    (net (code "60") (name "Net-(U107-A)") (class "Default")
      (node (ref "R110") (pin "2") (pinfunction "2_2") (pintype "passive"))
      (node (ref "U107") (pin "1") (pinfunction "A_1") (pintype "passive"))
    )
    (net (code "61") (name "Net-(U107-C-Pad4)") (class "Default")
      (node (ref "U107") (pin "4") (pinfunction "C_4") (pintype "passive"))
      (node (ref "V100") (pin "1") (pinfunction "1_1") (pintype "passive"))
    )
    (net (code "62") (name "Net-(U108-A)") (class "Default")
      (node (ref "R114") (pin "2") (pinfunction "2_2") (pintype "passive"))
      (node (ref "U108") (pin "1") (pinfunction "A_1") (pintype "passive"))
    )
    (net (code "63") (name "Net-(U108-C-Pad4)") (class "Default")
      (node (ref "U108") (pin "4") (pinfunction "C_4") (pintype "passive"))
      (node (ref "V101") (pin "1") (pinfunction "1_1") (pintype "passive"))
    )
    (net (code "64") (name "Net-(U109-EN)") (class "Default")
      (node (ref "R122") (pin "1") (pinfunction "1_1") (pintype "passive"))
      (node (ref "U109") (pin "1") (pinfunction "EN_1") (pintype "passive"))
    )
    (net (code "65") (name "Net-(X100-Shield)") (class "Default")
      (node (ref "R100") (pin "2") (pinfunction "2_2") (pintype "passive"))
      (node (ref "X100") (pin "Shell") (pinfunction "Shield_Shell") (pintype "passive"))
    )
    (net (code "66") (name "unconnected-(U100-PA03{slash}AIN0_1{slash}VREFA-Pad4)") (class "Default")
      (node (ref "U100") (pin "4") (pinfunction "PA03/AIN0_1/VREFA_4") (pintype "bidirectional+no_connect"))
    )
    (net (code "67") (name "unconnected-(U100-PA10{slash}AIN0_10{slash}COM0_2{slash}COM2_2-Pad19)") (class "Default")
      (node (ref "U100") (pin "19") (pinfunction "PA10/AIN0_10/COM0_2/COM2_2_19") (pintype "bidirectional+no_connect"))
    )
    (net (code "68") (name "unconnected-(U100-PA11{slash}AIN0_11{slash}COM0_3{slash}COM2_3-Pad20)") (class "Default")
      (node (ref "U100") (pin "20") (pinfunction "PA11/AIN0_11/COM0_3/COM2_3_20") (pintype "bidirectional+no_connect"))
    )
    (net (code "69") (name "unconnected-(U100-PA12{slash}COM2_0{slash}COM4_1-Pad29)") (class "Default")
      (node (ref "U100") (pin "29") (pinfunction "PA12/COM2_0/COM4_1_29") (pintype "bidirectional+no_connect"))
    )
    (net (code "70") (name "unconnected-(U100-PA13{slash}COM2_1{slash}COM4_0-Pad30)") (class "Default")
      (node (ref "U100") (pin "30") (pinfunction "PA13/COM2_1/COM4_0_30") (pintype "bidirectional+no_connect"))
    )
    (net (code "71") (name "unconnected-(U100-PA16{slash}COM1_0{slash}COM3_1-Pad35)") (class "Default")
      (node (ref "U100") (pin "35") (pinfunction "PA16/COM1_0/COM3_1_35") (pintype "bidirectional+no_connect"))
    )
    (net (code "72") (name "unconnected-(U100-PA17{slash}COM1_1{slash}COM3_0-Pad36)") (class "Default")
      (node (ref "U100") (pin "36") (pinfunction "PA17/COM1_1/COM3_0_36") (pintype "bidirectional+no_connect"))
    )
    (net (code "73") (name "unconnected-(U100-PA20{slash}COM5_2{slash}COM3_2-Pad41)") (class "Default")
      (node (ref "U100") (pin "41") (pinfunction "PA20/COM5_2/COM3_2_41") (pintype "bidirectional+no_connect"))
    )
    (net (code "74") (name "unconnected-(U100-PA21{slash}COM5_3{slash}COM3_3-Pad42)") (class "Default")
      (node (ref "U100") (pin "42") (pinfunction "PA21/COM5_3/COM3_3_42") (pintype "bidirectional+no_connect"))
    )
    (net (code "75") (name "unconnected-(U100-PA22{slash}COM5_1{slash}COM3_0{slash}CAN0_TX-Pad43)") (class "Default")
      (node (ref "U100") (pin "43") (pinfunction "PA22/COM5_1/COM3_0/CAN0_TX_43") (pintype "bidirectional+no_connect"))
    )
    (net (code "76") (name "unconnected-(U100-PA23{slash}COM5_0{slash}COM3_1{slash}CAN0_RX-Pad44)") (class "Default")
      (node (ref "U100") (pin "44") (pinfunction "PA23/COM5_0/COM3_1/CAN0_RX_44") (pintype "bidirectional+no_connect"))
    )
    (net (code "77") (name "unconnected-(U100-PA27-Pad51)") (class "Default")
      (node (ref "U100") (pin "51") (pinfunction "PA27_51") (pintype "bidirectional+no_connect"))
    )
    (net (code "78") (name "unconnected-(U100-PB05{slash}AIN1_7-Pad6)") (class "Default")
      (node (ref "U100") (pin "6") (pinfunction "PB05/AIN1_7_6") (pintype "bidirectional+no_connect"))
    )
    (net (code "79") (name "unconnected-(U100-PB06{slash}AIN1_8-Pad9)") (class "Default")
      (node (ref "U100") (pin "9") (pinfunction "PB06/AIN1_8_9") (pintype "bidirectional+no_connect"))
    )
    (net (code "80") (name "unconnected-(U100-PB07{slash}AIN1_9-Pad10)") (class "Default")
      (node (ref "U100") (pin "10") (pinfunction "PB07/AIN1_9_10") (pintype "bidirectional+no_connect"))
    )
    (net (code "81") (name "unconnected-(U100-PB08{slash}AIN0_2{slash}AIN1_0{slash}COM4_0-Pad11)") (class "Default")
      (node (ref "U100") (pin "11") (pinfunction "PB08/AIN0_2/AIN1_0/COM4_0_11") (pintype "bidirectional+no_connect"))
    )
    (net (code "82") (name "unconnected-(U100-PB10{slash}COM4_2-Pad23)") (class "Default")
      (node (ref "U100") (pin "23") (pinfunction "PB10/COM4_2_23") (pintype "bidirectional+no_connect"))
    )
    (net (code "83") (name "unconnected-(U100-PB11{slash}COM4_3-Pad24)") (class "Default")
      (node (ref "U100") (pin "24") (pinfunction "PB11/COM4_3_24") (pintype "bidirectional+no_connect"))
    )
    (net (code "84") (name "unconnected-(U100-PB12{slash}COM4_0{slash}CAN1_TX-Pad25)") (class "Default")
      (node (ref "U100") (pin "25") (pinfunction "PB12/COM4_0/CAN1_TX_25") (pintype "bidirectional+no_connect"))
    )
    (net (code "85") (name "unconnected-(U100-PB13{slash}COM4_1{slash}CAN1_RX-Pad26)") (class "Default")
      (node (ref "U100") (pin "26") (pinfunction "PB13/COM4_1/CAN1_RX_26") (pintype "bidirectional+no_connect"))
    )
    (net (code "86") (name "unconnected-(U100-PB14{slash}COM4_2{slash}CAN1_TX-Pad27)") (class "Default")
      (node (ref "U100") (pin "27") (pinfunction "PB14/COM4_2/CAN1_TX_27") (pintype "bidirectional+no_connect"))
    )
    (net (code "87") (name "unconnected-(U100-PB15{slash}COM4_3{slash}CAN1_RX-Pad28)") (class "Default")
      (node (ref "U100") (pin "28") (pinfunction "PB15/COM4_3/CAN1_RX_28") (pintype "bidirectional+no_connect"))
    )
    (net (code "88") (name "unconnected-(U100-PB22{slash}COM5_2{slash}COM1_2{slash}XIN1-Pad49)") (class "Default")
      (node (ref "U100") (pin "49") (pinfunction "PB22/COM5_2/COM1_2/XIN1_49") (pintype "bidirectional+no_connect"))
    )
    (net (code "89") (name "unconnected-(U100-PB23{slash}COM5_3{slash}COM1_3{slash}XOUT1-Pad50)") (class "Default")
      (node (ref "U100") (pin "50") (pinfunction "PB23/COM5_3/COM1_3/XOUT1_50") (pintype "bidirectional+no_connect"))
    )
    (net (code "90") (name "unconnected-(U100-PB31{slash}COM5_0{slash}COM7_1-Pad60)") (class "Default")
      (node (ref "U100") (pin "60") (pinfunction "PB31/COM5_0/COM7_1_60") (pintype "bidirectional+no_connect"))
    )
    (net (code "91") (name "unconnected-(U100-VSW-Pad55)") (class "Default")
      (node (ref "U100") (pin "55") (pinfunction "VSW_55") (pintype "passive+no_connect"))
    )
    (net (code "92") (name "unconnected-(U103-NC-Pad3)") (class "Default")
      (node (ref "U103") (pin "3") (pinfunction "NC_3") (pintype "passive+no_connect"))
    )
    (net (code "93") (name "unconnected-(U103-NC-Pad8)") (class "Default")
      (node (ref "U103") (pin "8") (pinfunction "NC_8") (pintype "passive+no_connect"))
    )
    (net (code "94") (name "unconnected-(U105-NC-Pad3)") (class "Default")
      (node (ref "U105") (pin "3") (pinfunction "NC_3") (pintype "passive+no_connect"))
    )
    (net (code "95") (name "unconnected-(U105-NC-Pad8)") (class "Default")
      (node (ref "U105") (pin "8") (pinfunction "NC_8") (pintype "passive+no_connect"))
    )
    (net (code "96") (name "unconnected-(X102-Pad1)") (class "Default")
      (node (ref "X102") (pin "1") (pinfunction "1_1") (pintype "passive"))
    )
    (net (code "97") (name "unconnected-(X102-Pad2)") (class "Default")
      (node (ref "X102") (pin "2") (pinfunction "2_2") (pintype "passive"))
    )
    (net (code "98") (name "unconnected-(X102-Pad4)") (class "Default")
      (node (ref "X102") (pin "4") (pinfunction "4_4") (pintype "passive"))
    )
    (net (code "99") (name "unconnected-(X102-Pad5)") (class "Default")
      (node (ref "X102") (pin "5") (pinfunction "5_5") (pintype "passive"))
    )
    (net (code "100") (name "unconnected-(X102-Pad9)") (class "Default")
      (node (ref "X102") (pin "9") (pinfunction "9_9") (pintype "passive"))
    )
    (net (code "101") (name "unconnected-(X102-PadSH)") (class "Default")
      (node (ref "X102") (pin "SH") (pinfunction "SH_SH") (pintype "passive"))
    )
    (net (code "102") (name "unconnected-(X104-KEY-Pad7)") (class "Default")
      (node (ref "X104") (pin "7") (pinfunction "KEY_7") (pintype "passive"))
    )
    (net (code "103") (name "unconnected-(X104-NC{slash}TDI-Pad8)") (class "Default")
      (node (ref "X104") (pin "8") (pinfunction "NC/TDI_8") (pintype "passive"))
    )
  )
)
